# radiomodul.net
KiCad netlist of a schematic drawn in EAGLE
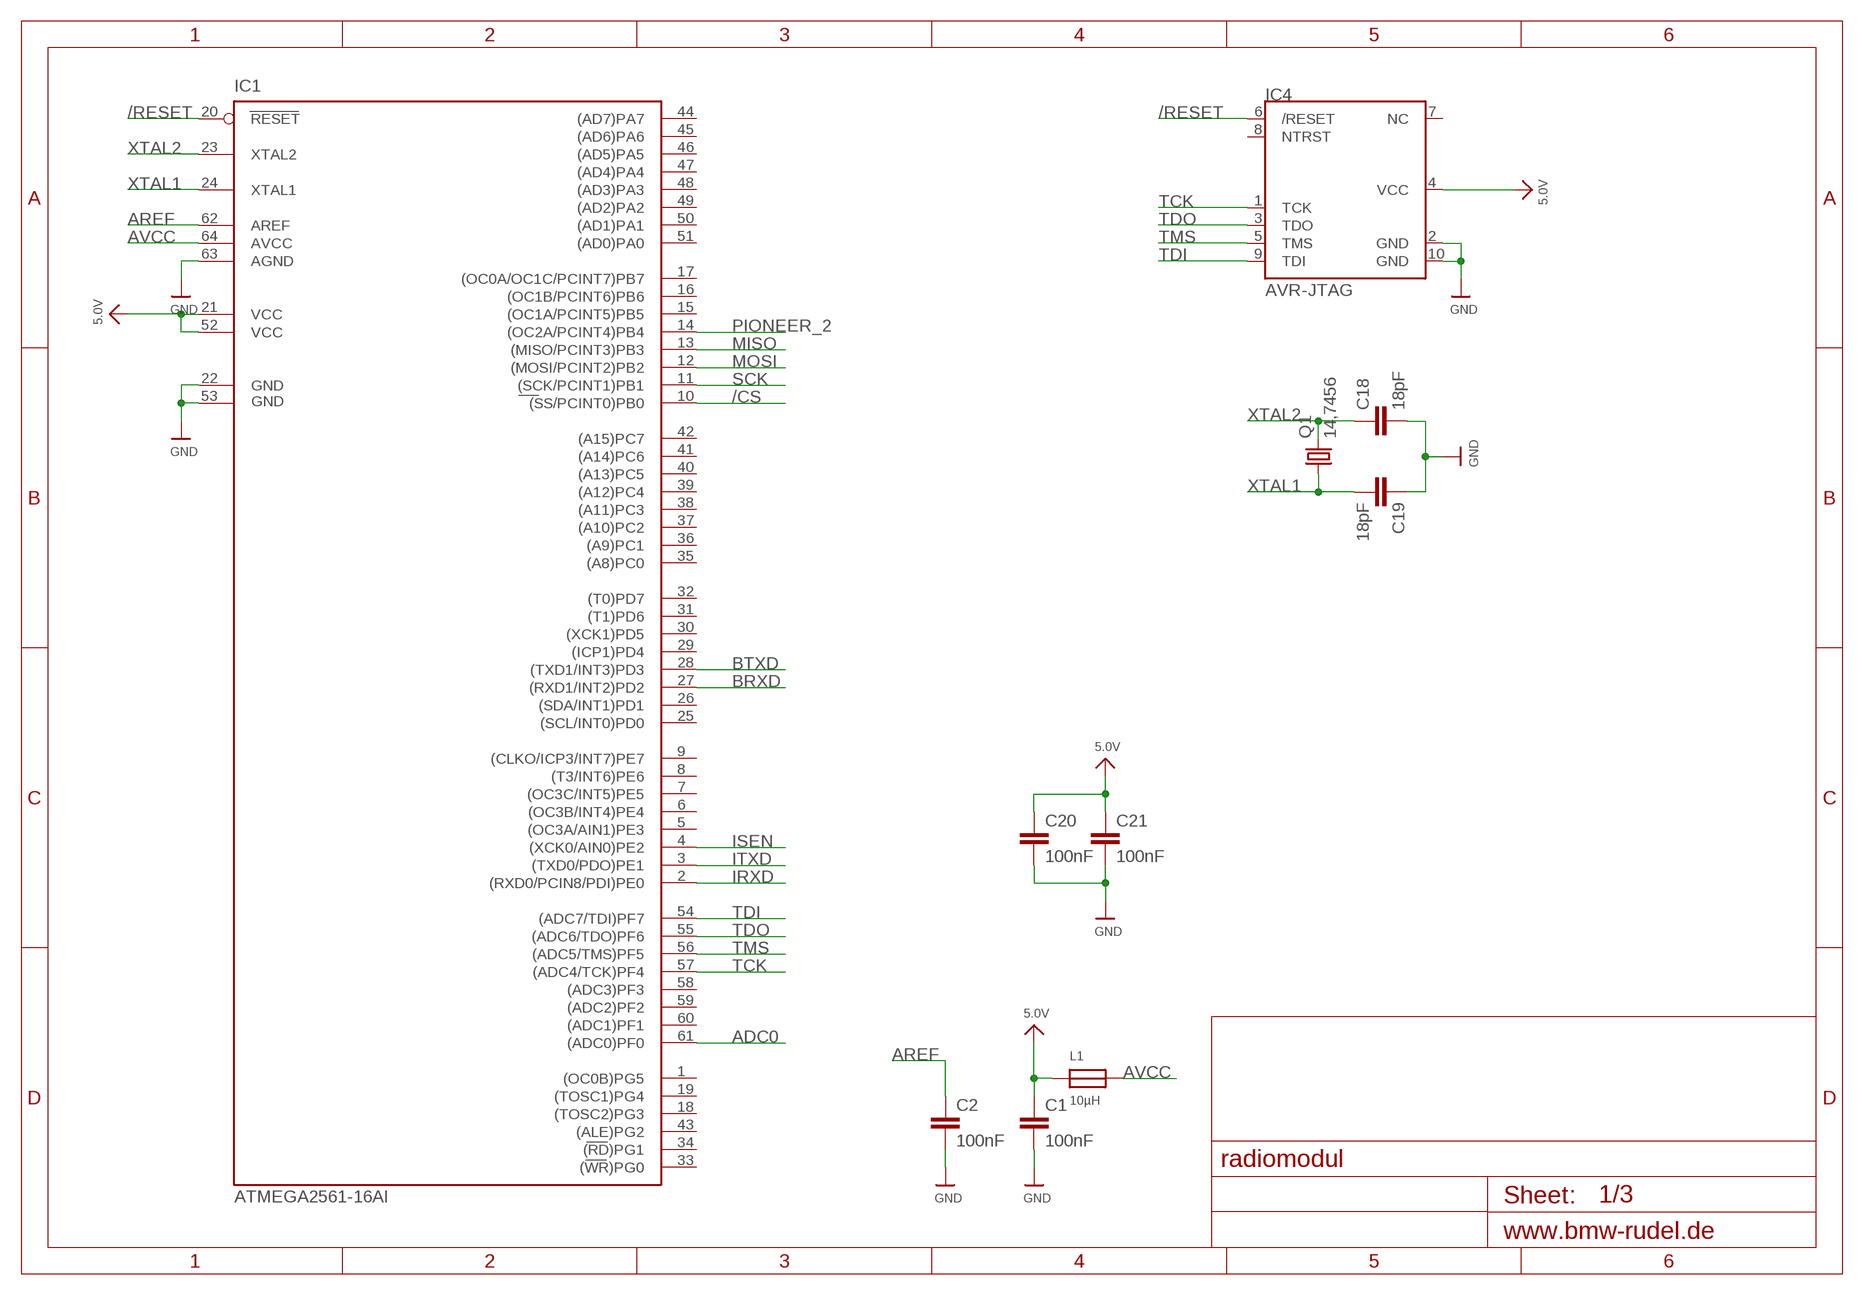
[diagram p0: schematic, sheet 1]
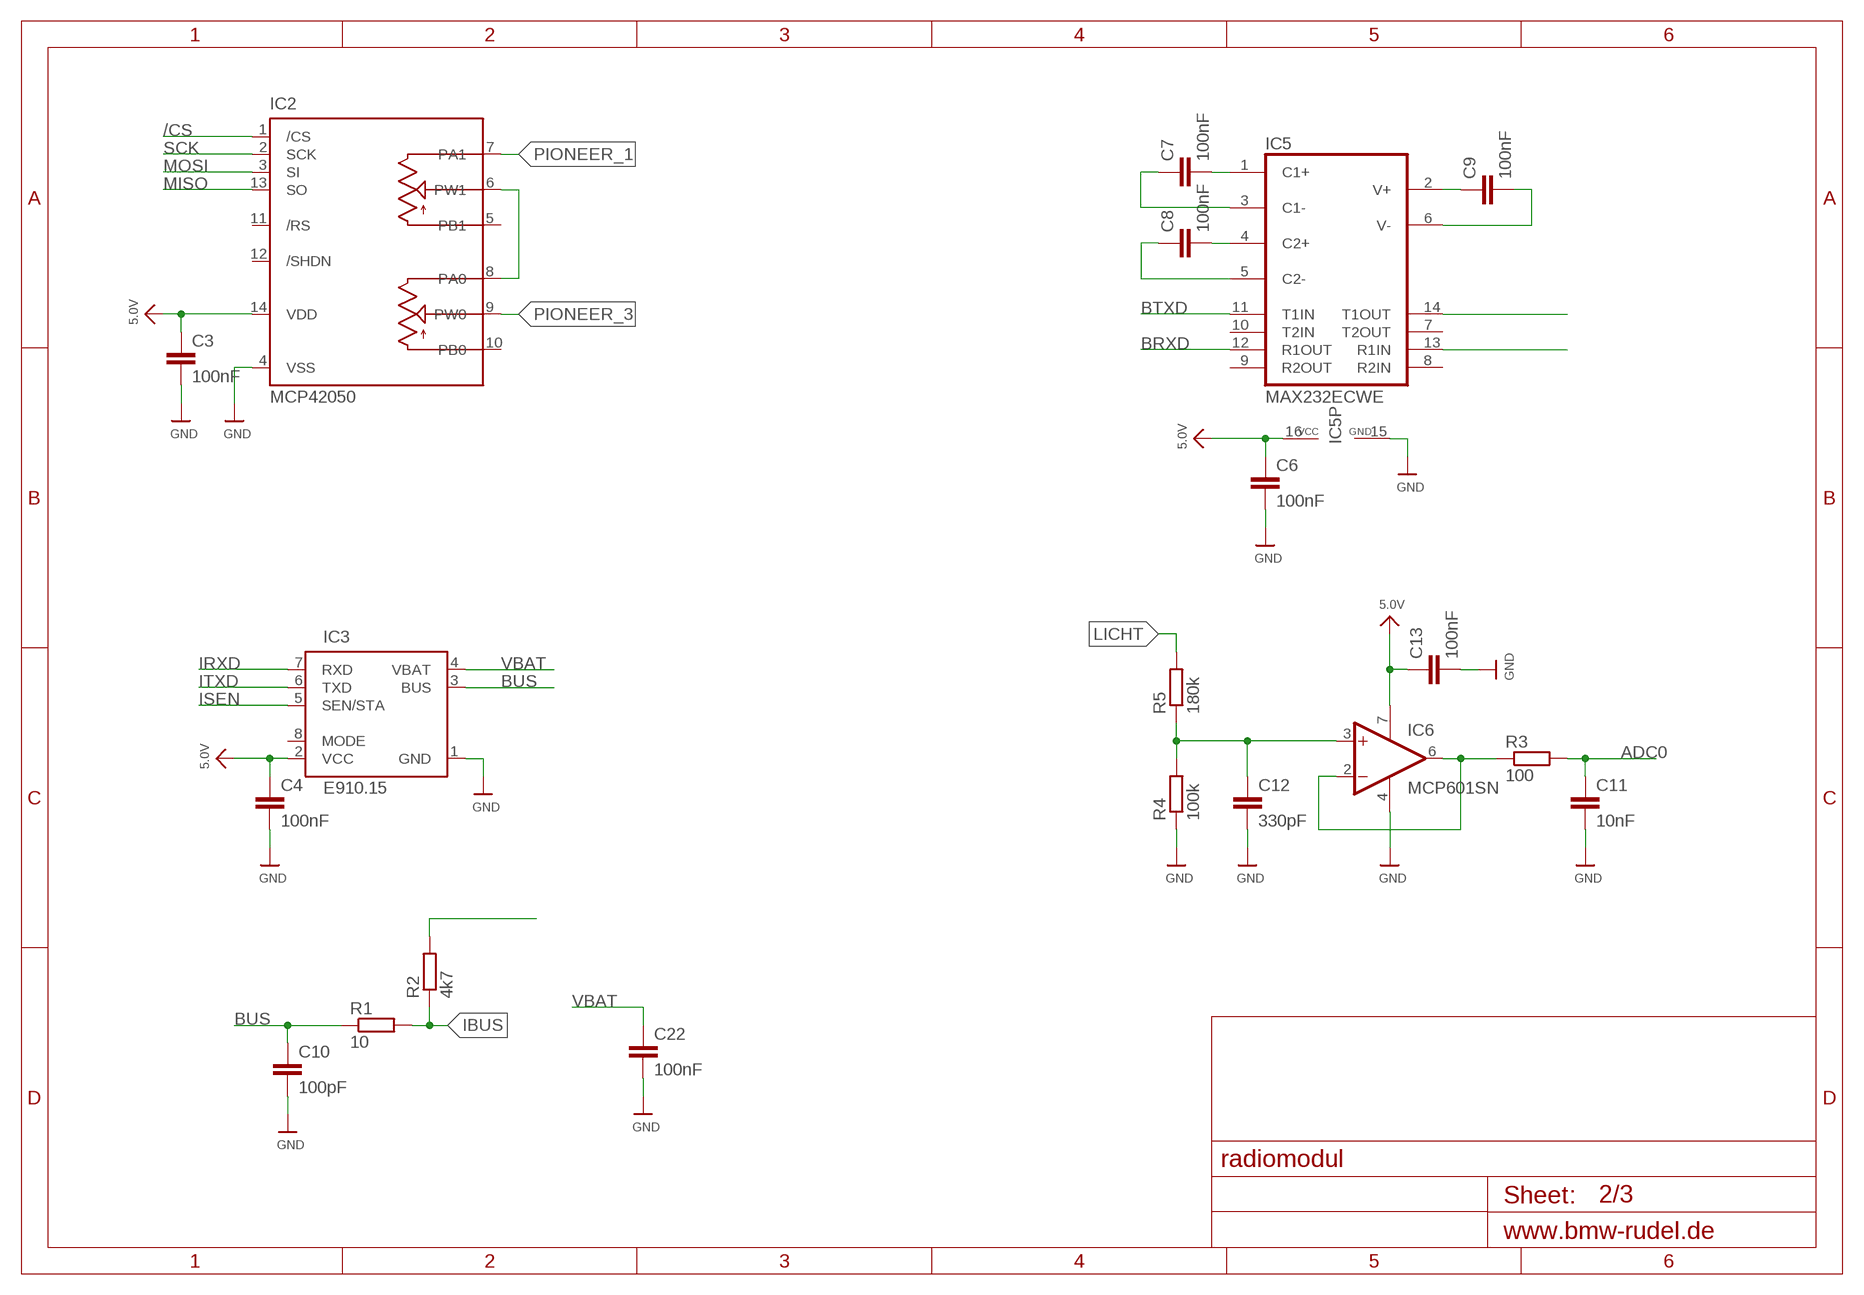
[diagram p1: schematic, sheet 2]
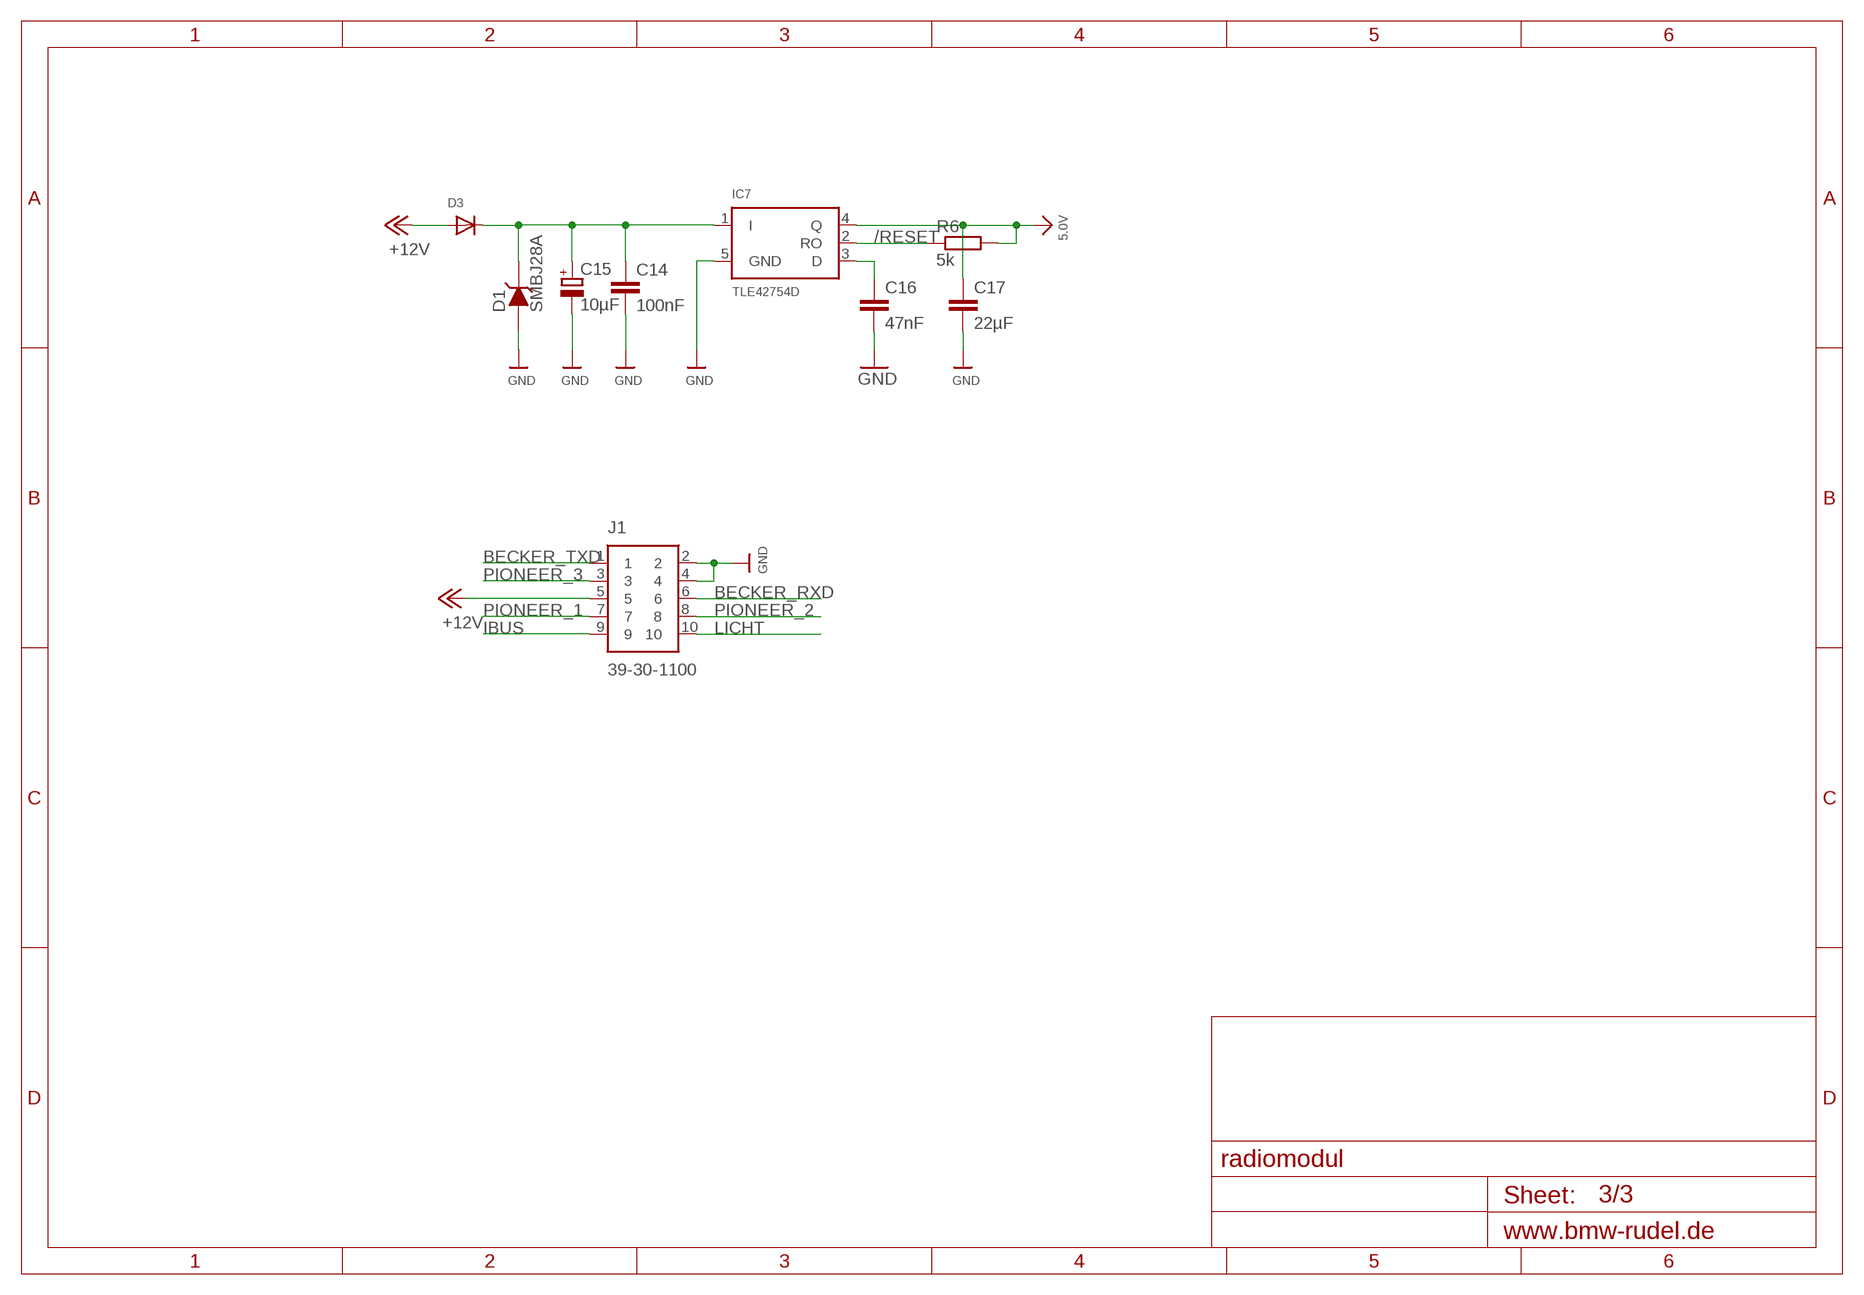
[diagram p2: schematic, sheet 3]

(export (version "E")
  (design (tool "Eeschema 10.0.6"))
  (components
    (comp (ref "C1")
      (value "100nF")
      (footprint "eagle-import:C0805")
      (libsource (lib "eagle-import") (part "C-EUC0805"))
    )
    (comp (ref "C2")
      (value "100nF")
      (footprint "eagle-import:C0805")
      (libsource (lib "eagle-import") (part "C-EUC0805"))
    )
    (comp (ref "C18")
      (value "18pF")
      (footprint "eagle-import:C0805")
      (libsource (lib "eagle-import") (part "C-EUC0805"))
    )
    (comp (ref "C19")
      (value "18pF")
      (footprint "eagle-import:C0805")
      (libsource (lib "eagle-import") (part "C-EUC0805"))
    )
    (comp (ref "C20")
      (value "100nF")
      (footprint "eagle-import:C0805")
      (libsource (lib "eagle-import") (part "C-EUC0805"))
    )
    (comp (ref "C21")
      (value "100nF")
      (footprint "eagle-import:C0805")
      (libsource (lib "eagle-import") (part "C-EUC0805"))
    )
    (comp (ref "IC1")
      (value "ATMEGA2561-16AI")
      (footprint "eagle-import:TQFP64")
      (libsource (lib "eagle-import") (part "ATMEGA2561AI-16"))
    )
    (comp (ref "IC4")
      (value "AVR-JTAG")
      (footprint "eagle-import:2X05_1.27MM_SMT")
      (libsource (lib "eagle-import") (part "AVR-JTAG"))
    )
    (comp (ref "L1")
      (value "10µH")
      (footprint "eagle-import:1206")
      (libsource (lib "eagle-import") (part "FERRITE1206"))
    )
    (comp (ref "Q1")
      (value "14,7456")
      (footprint "eagle-import:HC49UP")
      (libsource (lib "eagle-import") (part "CRYSTALHC49UP"))
    )
    (comp (ref "C3")
      (value "100nF")
      (footprint "eagle-import:C0805")
      (libsource (lib "eagle-import") (part "C-EUC0805"))
    )
    (comp (ref "C4")
      (value "100nF")
      (footprint "eagle-import:C0805")
      (libsource (lib "eagle-import") (part "C-EUC0805"))
    )
    (comp (ref "C6")
      (value "100nF")
      (footprint "eagle-import:C0805")
      (libsource (lib "eagle-import") (part "C-EUC0805"))
    )
    (comp (ref "C7")
      (value "100nF")
      (footprint "eagle-import:C0805")
      (libsource (lib "eagle-import") (part "C-EUC0805"))
    )
    (comp (ref "C8")
      (value "100nF")
      (footprint "eagle-import:C0805")
      (libsource (lib "eagle-import") (part "C-EUC0805"))
    )
    (comp (ref "C9")
      (value "100nF")
      (footprint "eagle-import:C0805")
      (libsource (lib "eagle-import") (part "C-EUC0805"))
    )
    (comp (ref "C10")
      (value "100pF")
      (footprint "eagle-import:C0805")
      (libsource (lib "eagle-import") (part "C-EUC0805"))
    )
    (comp (ref "C11")
      (value "10nF")
      (footprint "eagle-import:C0805")
      (libsource (lib "eagle-import") (part "C-EUC0805"))
    )
    (comp (ref "C12")
      (value "330pF")
      (footprint "eagle-import:C0805")
      (libsource (lib "eagle-import") (part "C-EUC0805"))
    )
    (comp (ref "C13")
      (value "100nF")
      (footprint "eagle-import:C0805")
      (libsource (lib "eagle-import") (part "C-EUC0805"))
    )
    (comp (ref "C22")
      (value "100nF")
      (footprint "eagle-import:C0805")
      (libsource (lib "eagle-import") (part "C-EUC0805"))
    )
    (comp (ref "IC2")
      (value "MCP42050")
      (footprint "eagle-import:SO-14")
      (libsource (lib "eagle-import") (part "MCP42050"))
    )
    (comp (ref "IC3")
      (value "E910.15")
      (footprint "eagle-import:SO8")
      (libsource (lib "eagle-import") (part "E910.15"))
    )
    (comp (ref "IC5")
      (value "MAX232ECWE")
      (footprint "eagle-import:SO16L")
      (fields (field (name "MF") "MAXIM") (field (name "MPN") "MAX232ECWE+"))
      (libsource (lib "eagle-import") (part "MAX232ECWE"))
    )
    (comp (ref "IC6")
      (value "MCP601SN")
      (footprint "eagle-import:SO08")
      (libsource (lib "eagle-import") (part "MCP601SN"))
    )
    (comp (ref "R1")
      (value "10")
      (footprint "eagle-import:R0805")
      (libsource (lib "eagle-import") (part "R-EU_R0805"))
    )
    (comp (ref "R2")
      (value "4k7")
      (footprint "eagle-import:R0805")
      (libsource (lib "eagle-import") (part "R-EU_R0805"))
    )
    (comp (ref "R3")
      (value "100")
      (footprint "eagle-import:R0805")
      (libsource (lib "eagle-import") (part "R-EU_R0805"))
    )
    (comp (ref "R4")
      (value "100k")
      (footprint "eagle-import:R0805")
      (libsource (lib "eagle-import") (part "R-EU_R0805"))
    )
    (comp (ref "R5")
      (value "180k")
      (footprint "eagle-import:R0805")
      (libsource (lib "eagle-import") (part "R-EU_R0805"))
    )
    (comp (ref "C14")
      (value "100nF")
      (footprint "eagle-import:C0805")
      (libsource (lib "eagle-import") (part "C-EUC0805"))
    )
    (comp (ref "C15")
      (value "10µF")
      (footprint "eagle-import:PANASONIC_D")
      (libsource (lib "eagle-import") (part "CPOL-EUD"))
    )
    (comp (ref "C16")
      (value "47nF")
      (footprint "eagle-import:C0805")
      (libsource (lib "eagle-import") (part "C-EUC0805"))
    )
    (comp (ref "C17")
      (value "22µF")
      (footprint "eagle-import:C1206")
      (libsource (lib "eagle-import") (part "C-EUC1206"))
    )
    (comp (ref "D1")
      (value "SMBJ28A")
      (footprint "eagle-import:DO-214AA")
      (libsource (lib "eagle-import") (part "P6SMBXXASMB"))
    )
    (comp (ref "D3")
      (value "DIODESMA")
      (footprint "eagle-import:SMADIODE")
      (libsource (lib "eagle-import") (part "DIODESMA"))
    )
    (comp (ref "IC7")
      (value "TLE42754D")
      (footprint "eagle-import:TO252-51")
      (libsource (lib "eagle-import") (part "TLE42754D"))
    )
    (comp (ref "J1")
      (value "39-30-1100")
      (footprint "eagle-import:39-30-1100")
      (fields (field (name "MOUSER_PART_NUMBER") "538-39-30-1100") (field (name "RS_PART_NUMBER") "5109871P"))
      (libsource (lib "eagle-import") (part "39-30-1100"))
    )
    (comp (ref "R6")
      (value "5k")
      (footprint "eagle-import:R0805")
      (libsource (lib "eagle-import") (part "R-EU_R0805"))
    )
  )
  (nets
    (net (code "1") (name "+12V") (class "Default")
      (node (ref "D3") (pin "A") (pinfunction "A_A") (pintype "passive"))
      (node (ref "J1") (pin "5") (pinfunction "5_5") (pintype "bidirectional"))
    )
    (net (code "2") (name "5.0V") (class "Default")
      (node (ref "C1") (pin "1") (pinfunction "1_1") (pintype "passive"))
      (node (ref "C13") (pin "1") (pinfunction "1_1") (pintype "passive"))
      (node (ref "C17") (pin "1") (pinfunction "1_1") (pintype "passive"))
      (node (ref "C20") (pin "1") (pinfunction "1_1") (pintype "passive"))
      (node (ref "C21") (pin "1") (pinfunction "1_1") (pintype "passive"))
      (node (ref "C3") (pin "1") (pinfunction "1_1") (pintype "passive"))
      (node (ref "C4") (pin "1") (pinfunction "1_1") (pintype "passive"))
      (node (ref "C6") (pin "1") (pinfunction "1_1") (pintype "passive"))
      (node (ref "IC1") (pin "21") (pinfunction "VCC_21") (pintype "power_in"))
      (node (ref "IC1") (pin "52") (pinfunction "VCC1_52") (pintype "power_in"))
      (node (ref "IC2") (pin "14") (pinfunction "VDD_14") (pintype "power_in"))
      (node (ref "IC3") (pin "2") (pinfunction "VCC_2") (pintype "power_in"))
      (node (ref "IC4") (pin "4") (pinfunction "VCC_4") (pintype "bidirectional"))
      (node (ref "IC5") (pin "16") (pinfunction "VCC_16") (pintype "power_in"))
      (node (ref "IC6") (pin "7") (pinfunction "V+_7") (pintype "power_in"))
      (node (ref "IC7") (pin "4") (pinfunction "Q_4") (pintype "bidirectional"))
      (node (ref "L1") (pin "1") (pinfunction "P$1_1") (pintype "bidirectional"))
      (node (ref "R6") (pin "2") (pinfunction "2_2") (pintype "passive"))
    )
    (net (code "3") (name "ADC0") (class "Default")
      (node (ref "C11") (pin "1") (pinfunction "1_1") (pintype "passive"))
      (node (ref "IC1") (pin "61") (pinfunction "(ADC0)PF0_61") (pintype "bidirectional"))
      (node (ref "R3") (pin "2") (pinfunction "2_2") (pintype "passive"))
    )
    (net (code "4") (name "AREF") (class "Default")
      (node (ref "C2") (pin "1") (pinfunction "1_1") (pintype "passive"))
      (node (ref "IC1") (pin "62") (pinfunction "AREF_62") (pintype "bidirectional"))
    )
    (net (code "5") (name "AVCC") (class "Default")
      (node (ref "IC1") (pin "64") (pinfunction "AVCC_64") (pintype "power_in"))
      (node (ref "L1") (pin "2") (pinfunction "P$2_2") (pintype "bidirectional"))
    )
    (net (code "6") (name "BECKER_RXD") (class "Default")
      (node (ref "IC5") (pin "13") (pinfunction "R1IN_13") (pintype "input"))
      (node (ref "J1") (pin "6") (pinfunction "6_6") (pintype "bidirectional"))
    )
    (net (code "7") (name "BECKER_TXD") (class "Default")
      (node (ref "IC5") (pin "14") (pinfunction "T1OUT_14") (pintype "output"))
      (node (ref "J1") (pin "1") (pinfunction "1_1") (pintype "bidirectional"))
    )
    (net (code "8") (name "BRXD") (class "Default")
      (node (ref "IC1") (pin "27") (pinfunction "(RXD1/INT2)PD2_27") (pintype "bidirectional"))
      (node (ref "IC5") (pin "12") (pinfunction "R1OUT_12") (pintype "output"))
    )
    (net (code "9") (name "BTXD") (class "Default")
      (node (ref "IC1") (pin "28") (pinfunction "(TXD1/INT3)PD3_28") (pintype "bidirectional"))
      (node (ref "IC5") (pin "11") (pinfunction "T1IN_11") (pintype "input"))
    )
    (net (code "10") (name "BUS") (class "Default")
      (node (ref "C10") (pin "1") (pinfunction "1_1") (pintype "passive"))
      (node (ref "IC3") (pin "3") (pinfunction "BUS_3") (pintype "bidirectional"))
      (node (ref "R1") (pin "1") (pinfunction "1_1") (pintype "passive"))
    )
    (net (code "11") (name "GND") (class "Default")
      (node (ref "C1") (pin "2") (pinfunction "2_2") (pintype "passive"))
      (node (ref "C10") (pin "2") (pinfunction "2_2") (pintype "passive"))
      (node (ref "C11") (pin "2") (pinfunction "2_2") (pintype "passive"))
      (node (ref "C12") (pin "2") (pinfunction "2_2") (pintype "passive"))
      (node (ref "C13") (pin "2") (pinfunction "2_2") (pintype "passive"))
      (node (ref "C14") (pin "2") (pinfunction "2_2") (pintype "passive"))
      (node (ref "C15") (pin "-") (pinfunction "-_-") (pintype "passive"))
      (node (ref "C16") (pin "2") (pinfunction "2_2") (pintype "passive"))
      (node (ref "C17") (pin "2") (pinfunction "2_2") (pintype "passive"))
      (node (ref "C18") (pin "2") (pinfunction "2_2") (pintype "passive"))
      (node (ref "C19") (pin "1") (pinfunction "1_1") (pintype "passive"))
      (node (ref "C2") (pin "2") (pinfunction "2_2") (pintype "passive"))
      (node (ref "C20") (pin "2") (pinfunction "2_2") (pintype "passive"))
      (node (ref "C21") (pin "2") (pinfunction "2_2") (pintype "passive"))
      (node (ref "C22") (pin "2") (pinfunction "2_2") (pintype "passive"))
      (node (ref "C3") (pin "2") (pinfunction "2_2") (pintype "passive"))
      (node (ref "C4") (pin "2") (pinfunction "2_2") (pintype "passive"))
      (node (ref "C6") (pin "2") (pinfunction "2_2") (pintype "passive"))
      (node (ref "D1") (pin "P$2") (pinfunction "A_P$2") (pintype "passive"))
      (node (ref "IC1") (pin "22") (pinfunction "GND_22") (pintype "power_in"))
      (node (ref "IC1") (pin "53") (pinfunction "GND1_53") (pintype "power_in"))
      (node (ref "IC1") (pin "63") (pinfunction "AGND_63") (pintype "power_in"))
      (node (ref "IC2") (pin "4") (pinfunction "VSS_4") (pintype "power_in"))
      (node (ref "IC3") (pin "1") (pinfunction "GND_1") (pintype "power_in"))
      (node (ref "IC4") (pin "10") (pinfunction "GND_10") (pintype "bidirectional"))
      (node (ref "IC4") (pin "2") (pinfunction "GND_2") (pintype "bidirectional"))
      (node (ref "IC5") (pin "15") (pinfunction "GND_15") (pintype "power_in"))
      (node (ref "IC6") (pin "4") (pinfunction "V-_4") (pintype "power_in"))
      (node (ref "IC7") (pin "5") (pinfunction "GND_5") (pintype "bidirectional"))
      (node (ref "J1") (pin "2") (pinfunction "2_2") (pintype "bidirectional"))
      (node (ref "J1") (pin "4") (pinfunction "4_4") (pintype "bidirectional"))
      (node (ref "R4") (pin "1") (pinfunction "1_1") (pintype "passive"))
    )
    (net (code "12") (name "IBUS") (class "Default")
      (node (ref "J1") (pin "9") (pinfunction "9_9") (pintype "bidirectional"))
      (node (ref "R1") (pin "2") (pinfunction "2_2") (pintype "passive"))
      (node (ref "R2") (pin "1") (pinfunction "1_1") (pintype "passive"))
    )
    (net (code "13") (name "IRXD") (class "Default")
      (node (ref "IC1") (pin "2") (pinfunction "(RXD0/PCIN8/PDI)PE0_2") (pintype "bidirectional"))
      (node (ref "IC3") (pin "7") (pinfunction "RXD_7") (pintype "output"))
    )
    (net (code "14") (name "ISEN") (class "Default")
      (node (ref "IC1") (pin "4") (pinfunction "(XCK0/AIN0)PE2_4") (pintype "bidirectional"))
      (node (ref "IC3") (pin "5") (pinfunction "SEN/STA_5") (pintype "bidirectional"))
    )
    (net (code "15") (name "ITXD") (class "Default")
      (node (ref "IC1") (pin "3") (pinfunction "(TXD0/PDO)PE1_3") (pintype "bidirectional"))
      (node (ref "IC3") (pin "6") (pinfunction "TXD_6") (pintype "input"))
    )
    (net (code "16") (name "LICHT") (class "Default")
      (node (ref "J1") (pin "10") (pinfunction "10_10") (pintype "bidirectional"))
      (node (ref "R5") (pin "2") (pinfunction "2_2") (pintype "passive"))
    )
    (net (code "17") (name "MISO") (class "Default")
      (node (ref "IC1") (pin "13") (pinfunction "(MISO/PCINT3)PB3_13") (pintype "bidirectional"))
      (node (ref "IC2") (pin "13") (pinfunction "SO_13") (pintype "output"))
    )
    (net (code "18") (name "MOSI") (class "Default")
      (node (ref "IC1") (pin "12") (pinfunction "(MOSI/PCINT2)PB2_12") (pintype "bidirectional"))
      (node (ref "IC2") (pin "3") (pinfunction "SI_3") (pintype "input"))
    )
    (net (code "19") (name "Net-(IC2-PA0)") (class "Default")
      (node (ref "IC2") (pin "6") (pinfunction "PW1_6") (pintype "bidirectional"))
      (node (ref "IC2") (pin "8") (pinfunction "PA0_8") (pintype "bidirectional"))
    )
    (net (code "20") (name "Net-(IC5A-C1+)") (class "Default")
      (node (ref "C7") (pin "2") (pinfunction "2_2") (pintype "passive"))
      (node (ref "IC5") (pin "1") (pinfunction "C1+_1") (pintype "bidirectional"))
    )
    (net (code "21") (name "Net-(IC5A-C1-)") (class "Default")
      (node (ref "C7") (pin "1") (pinfunction "1_1") (pintype "passive"))
      (node (ref "IC5") (pin "3") (pinfunction "C1-_3") (pintype "bidirectional"))
    )
    (net (code "22") (name "Net-(IC5A-C2+)") (class "Default")
      (node (ref "C8") (pin "2") (pinfunction "2_2") (pintype "passive"))
      (node (ref "IC5") (pin "4") (pinfunction "C2+_4") (pintype "bidirectional"))
    )
    (net (code "23") (name "Net-(IC5A-C2-)") (class "Default")
      (node (ref "C8") (pin "1") (pinfunction "1_1") (pintype "passive"))
      (node (ref "IC5") (pin "5") (pinfunction "C2-_5") (pintype "bidirectional"))
    )
    (net (code "24") (name "Net-(IC5A-V+)") (class "Default")
      (node (ref "C9") (pin "1") (pinfunction "1_1") (pintype "passive"))
      (node (ref "IC5") (pin "2") (pinfunction "V+_2") (pintype "bidirectional"))
    )
    (net (code "25") (name "Net-(IC5A-V-)") (class "Default")
      (node (ref "C9") (pin "2") (pinfunction "2_2") (pintype "passive"))
      (node (ref "IC5") (pin "6") (pinfunction "V-_6") (pintype "bidirectional"))
    )
    (net (code "26") (name "Net-(IC6-+IN)") (class "Default")
      (node (ref "C12") (pin "1") (pinfunction "1_1") (pintype "passive"))
      (node (ref "IC6") (pin "3") (pinfunction "+IN_3") (pintype "input"))
      (node (ref "R4") (pin "2") (pinfunction "2_2") (pintype "passive"))
      (node (ref "R5") (pin "1") (pinfunction "1_1") (pintype "passive"))
    )
    (net (code "27") (name "Net-(IC6--IN)") (class "Default")
      (node (ref "IC6") (pin "2") (pinfunction "-IN_2") (pintype "input"))
      (node (ref "IC6") (pin "6") (pinfunction "OUT_6") (pintype "output"))
      (node (ref "R3") (pin "1") (pinfunction "1_1") (pintype "passive"))
    )
    (net (code "28") (name "Net-(IC7-D)") (class "Default")
      (node (ref "C16") (pin "1") (pinfunction "1_1") (pintype "passive"))
      (node (ref "IC7") (pin "3") (pinfunction "D_3") (pintype "bidirectional"))
    )
    (net (code "29") (name "PIONEER_1") (class "Default")
      (node (ref "IC2") (pin "7") (pinfunction "PA1_7") (pintype "bidirectional"))
      (node (ref "J1") (pin "7") (pinfunction "7_7") (pintype "bidirectional"))
    )
    (net (code "30") (name "PIONEER_2") (class "Default")
      (node (ref "IC1") (pin "14") (pinfunction "(OC2A/PCINT4)PB4_14") (pintype "bidirectional"))
      (node (ref "J1") (pin "8") (pinfunction "8_8") (pintype "bidirectional"))
    )
    (net (code "31") (name "PIONEER_3") (class "Default")
      (node (ref "IC2") (pin "9") (pinfunction "PW0_9") (pintype "bidirectional"))
      (node (ref "J1") (pin "3") (pinfunction "3_3") (pintype "bidirectional"))
    )
    (net (code "32") (name "SAFT") (class "Default")
      (node (ref "C14") (pin "1") (pinfunction "1_1") (pintype "passive"))
      (node (ref "C15") (pin "+") (pinfunction "+_+") (pintype "passive"))
      (node (ref "D1") (pin "P$1") (pinfunction "C_P$1") (pintype "passive"))
      (node (ref "D3") (pin "C") (pinfunction "C_C") (pintype "passive"))
      (node (ref "IC7") (pin "1") (pinfunction "I_1") (pintype "bidirectional"))
      (node (ref "R2") (pin "2") (pinfunction "2_2") (pintype "passive"))
    )
    (net (code "33") (name "SCK") (class "Default")
      (node (ref "IC1") (pin "11") (pinfunction "(SCK/PCINT1)PB1_11") (pintype "bidirectional"))
      (node (ref "IC2") (pin "2") (pinfunction "SCK_2") (pintype "input"))
    )
    (net (code "34") (name "TCK") (class "Default")
      (node (ref "IC1") (pin "57") (pinfunction "(ADC4/TCK)PF4_57") (pintype "bidirectional"))
      (node (ref "IC4") (pin "1") (pinfunction "TCK_1") (pintype "bidirectional"))
    )
    (net (code "35") (name "TDI") (class "Default")
      (node (ref "IC1") (pin "54") (pinfunction "(ADC7/TDI)PF7_54") (pintype "bidirectional"))
      (node (ref "IC4") (pin "9") (pinfunction "TDI_9") (pintype "bidirectional"))
    )
    (net (code "36") (name "TDO") (class "Default")
      (node (ref "IC1") (pin "55") (pinfunction "(ADC6/TDO)PF6_55") (pintype "bidirectional"))
      (node (ref "IC4") (pin "3") (pinfunction "TDO_3") (pintype "bidirectional"))
    )
    (net (code "37") (name "TMS") (class "Default")
      (node (ref "IC1") (pin "56") (pinfunction "(ADC5/TMS)PF5_56") (pintype "bidirectional"))
      (node (ref "IC4") (pin "5") (pinfunction "TMS_5") (pintype "bidirectional"))
    )
    (net (code "38") (name "VBAT") (class "Default")
      (node (ref "C22") (pin "1") (pinfunction "1_1") (pintype "passive"))
      (node (ref "IC3") (pin "4") (pinfunction "VBAT_4") (pintype "power_in"))
    )
    (net (code "39") (name "XTAL1") (class "Default")
      (node (ref "C19") (pin "2") (pinfunction "2_2") (pintype "passive"))
      (node (ref "IC1") (pin "24") (pinfunction "XTAL1_24") (pintype "input"))
      (node (ref "Q1") (pin "1") (pinfunction "1_1") (pintype "passive"))
    )
    (net (code "40") (name "XTAL2") (class "Default")
      (node (ref "C18") (pin "1") (pinfunction "1_1") (pintype "passive"))
      (node (ref "IC1") (pin "23") (pinfunction "XTAL2_23") (pintype "output"))
      (node (ref "Q1") (pin "2") (pinfunction "2_2") (pintype "passive"))
    )
    (net (code "41") (name "unconnected-(IC1-(A8)PC0-Pad35)") (class "Default")
      (node (ref "IC1") (pin "35") (pinfunction "(A8)PC0_35") (pintype "bidirectional"))
    )
    (net (code "42") (name "unconnected-(IC1-(A9)PC1-Pad36)") (class "Default")
      (node (ref "IC1") (pin "36") (pinfunction "(A9)PC1_36") (pintype "bidirectional"))
    )
    (net (code "43") (name "unconnected-(IC1-(A10)PC2-Pad37)") (class "Default")
      (node (ref "IC1") (pin "37") (pinfunction "(A10)PC2_37") (pintype "bidirectional"))
    )
    (net (code "44") (name "unconnected-(IC1-(A11)PC3-Pad38)") (class "Default")
      (node (ref "IC1") (pin "38") (pinfunction "(A11)PC3_38") (pintype "bidirectional"))
    )
    (net (code "45") (name "unconnected-(IC1-(A12)PC4-Pad39)") (class "Default")
      (node (ref "IC1") (pin "39") (pinfunction "(A12)PC4_39") (pintype "bidirectional"))
    )
    (net (code "46") (name "unconnected-(IC1-(A13)PC5-Pad40)") (class "Default")
      (node (ref "IC1") (pin "40") (pinfunction "(A13)PC5_40") (pintype "bidirectional"))
    )
    (net (code "47") (name "unconnected-(IC1-(A14)PC6-Pad41)") (class "Default")
      (node (ref "IC1") (pin "41") (pinfunction "(A14)PC6_41") (pintype "bidirectional"))
    )
    (net (code "48") (name "unconnected-(IC1-(A15)PC7-Pad42)") (class "Default")
      (node (ref "IC1") (pin "42") (pinfunction "(A15)PC7_42") (pintype "bidirectional"))
    )
    (net (code "49") (name "unconnected-(IC1-(AD0)PA0-Pad51)") (class "Default")
      (node (ref "IC1") (pin "51") (pinfunction "(AD0)PA0_51") (pintype "bidirectional"))
    )
    (net (code "50") (name "unconnected-(IC1-(AD1)PA1-Pad50)") (class "Default")
      (node (ref "IC1") (pin "50") (pinfunction "(AD1)PA1_50") (pintype "bidirectional"))
    )
    (net (code "51") (name "unconnected-(IC1-(AD2)PA2-Pad49)") (class "Default")
      (node (ref "IC1") (pin "49") (pinfunction "(AD2)PA2_49") (pintype "bidirectional"))
    )
    (net (code "52") (name "unconnected-(IC1-(AD3)PA3-Pad48)") (class "Default")
      (node (ref "IC1") (pin "48") (pinfunction "(AD3)PA3_48") (pintype "bidirectional"))
    )
    (net (code "53") (name "unconnected-(IC1-(AD4)PA4-Pad47)") (class "Default")
      (node (ref "IC1") (pin "47") (pinfunction "(AD4)PA4_47") (pintype "bidirectional"))
    )
    (net (code "54") (name "unconnected-(IC1-(AD5)PA5-Pad46)") (class "Default")
      (node (ref "IC1") (pin "46") (pinfunction "(AD5)PA5_46") (pintype "bidirectional"))
    )
    (net (code "55") (name "unconnected-(IC1-(AD6)PA6-Pad45)") (class "Default")
      (node (ref "IC1") (pin "45") (pinfunction "(AD6)PA6_45") (pintype "bidirectional"))
    )
    (net (code "56") (name "unconnected-(IC1-(AD7)PA7-Pad44)") (class "Default")
      (node (ref "IC1") (pin "44") (pinfunction "(AD7)PA7_44") (pintype "bidirectional"))
    )
    (net (code "57") (name "unconnected-(IC1-(ADC1)PF1-Pad60)") (class "Default")
      (node (ref "IC1") (pin "60") (pinfunction "(ADC1)PF1_60") (pintype "bidirectional"))
    )
    (net (code "58") (name "unconnected-(IC1-(ADC2)PF2-Pad59)") (class "Default")
      (node (ref "IC1") (pin "59") (pinfunction "(ADC2)PF2_59") (pintype "bidirectional"))
    )
    (net (code "59") (name "unconnected-(IC1-(ADC3)PF3-Pad58)") (class "Default")
      (node (ref "IC1") (pin "58") (pinfunction "(ADC3)PF3_58") (pintype "bidirectional"))
    )
    (net (code "60") (name "unconnected-(IC1-(ALE)PG2-Pad43)") (class "Default")
      (node (ref "IC1") (pin "43") (pinfunction "(ALE)PG2_43") (pintype "bidirectional"))
    )
    (net (code "61") (name "unconnected-(IC1-(CLKO{slash}ICP3{slash}INT7)PE7-Pad9)") (class "Default")
      (node (ref "IC1") (pin "9") (pinfunction "(CLKO/ICP3/INT7)PE7_9") (pintype "bidirectional"))
    )
    (net (code "62") (name "unconnected-(IC1-(ICP1)PD4-Pad29)") (class "Default")
      (node (ref "IC1") (pin "29") (pinfunction "(ICP1)PD4_29") (pintype "bidirectional"))
    )
    (net (code "63") (name "unconnected-(IC1-(OC0A{slash}OC1C{slash}PCINT7)PB7-Pad17)") (class "Default")
      (node (ref "IC1") (pin "17") (pinfunction "(OC0A/OC1C/PCINT7)PB7_17") (pintype "bidirectional"))
    )
    (net (code "64") (name "unconnected-(IC1-(OC0B)PG5-Pad1)") (class "Default")
      (node (ref "IC1") (pin "1") (pinfunction "(OC0B)PG5_1") (pintype "bidirectional"))
    )
    (net (code "65") (name "unconnected-(IC1-(OC1A{slash}PCINT5)PB5-Pad15)") (class "Default")
      (node (ref "IC1") (pin "15") (pinfunction "(OC1A/PCINT5)PB5_15") (pintype "bidirectional"))
    )
    (net (code "66") (name "unconnected-(IC1-(OC1B{slash}PCINT6)PB6-Pad16)") (class "Default")
      (node (ref "IC1") (pin "16") (pinfunction "(OC1B/PCINT6)PB6_16") (pintype "bidirectional"))
    )
    (net (code "67") (name "unconnected-(IC1-(OC3A{slash}AIN1)PE3-Pad5)") (class "Default")
      (node (ref "IC1") (pin "5") (pinfunction "(OC3A/AIN1)PE3_5") (pintype "bidirectional"))
    )
    (net (code "68") (name "unconnected-(IC1-(OC3B{slash}INT4)PE4-Pad6)") (class "Default")
      (node (ref "IC1") (pin "6") (pinfunction "(OC3B/INT4)PE4_6") (pintype "bidirectional"))
    )
    (net (code "69") (name "unconnected-(IC1-(OC3C{slash}INT5)PE5-Pad7)") (class "Default")
      (node (ref "IC1") (pin "7") (pinfunction "(OC3C/INT5)PE5_7") (pintype "bidirectional"))
    )
    (net (code "70") (name "unconnected-(IC1-(RD)PG1-Pad34)") (class "Default")
      (node (ref "IC1") (pin "34") (pinfunction "(RD)PG1_34") (pintype "bidirectional"))
    )
    (net (code "71") (name "unconnected-(IC1-(SCL{slash}INT0)PD0-Pad25)") (class "Default")
      (node (ref "IC1") (pin "25") (pinfunction "(SCL/INT0)PD0_25") (pintype "bidirectional"))
    )
    (net (code "72") (name "unconnected-(IC1-(SDA{slash}INT1)PD1-Pad26)") (class "Default")
      (node (ref "IC1") (pin "26") (pinfunction "(SDA/INT1)PD1_26") (pintype "bidirectional"))
    )
    (net (code "73") (name "unconnected-(IC1-(T0)PD7-Pad32)") (class "Default")
      (node (ref "IC1") (pin "32") (pinfunction "(T0)PD7_32") (pintype "bidirectional"))
    )
    (net (code "74") (name "unconnected-(IC1-(T1)PD6-Pad31)") (class "Default")
      (node (ref "IC1") (pin "31") (pinfunction "(T1)PD6_31") (pintype "bidirectional"))
    )
    (net (code "75") (name "unconnected-(IC1-(T3{slash}INT6)PE6-Pad8)") (class "Default")
      (node (ref "IC1") (pin "8") (pinfunction "(T3/INT6)PE6_8") (pintype "bidirectional"))
    )
    (net (code "76") (name "unconnected-(IC1-(TOSC1)PG4-Pad19)") (class "Default")
      (node (ref "IC1") (pin "19") (pinfunction "(TOSC1)PG4_19") (pintype "bidirectional"))
    )
    (net (code "77") (name "unconnected-(IC1-(TOSC2)PG3-Pad18)") (class "Default")
      (node (ref "IC1") (pin "18") (pinfunction "(TOSC2)PG3_18") (pintype "bidirectional"))
    )
    (net (code "78") (name "unconnected-(IC1-(WR)PG0-Pad33)") (class "Default")
      (node (ref "IC1") (pin "33") (pinfunction "(WR)PG0_33") (pintype "bidirectional"))
    )
    (net (code "79") (name "unconnected-(IC1-(XCK1)PD5-Pad30)") (class "Default")
      (node (ref "IC1") (pin "30") (pinfunction "(XCK1)PD5_30") (pintype "bidirectional"))
    )
    (net (code "80") (name "unconnected-(IC2-PB0-Pad10)") (class "Default")
      (node (ref "IC2") (pin "10") (pinfunction "PB0_10") (pintype "bidirectional"))
    )
    (net (code "81") (name "unconnected-(IC2-PB1-Pad5)") (class "Default")
      (node (ref "IC2") (pin "5") (pinfunction "PB1_5") (pintype "bidirectional"))
    )
    (net (code "82") (name "unconnected-(IC2-{slash}RS-Pad11)") (class "Default")
      (node (ref "IC2") (pin "11") (pinfunction "/RS_11") (pintype "input"))
    )
    (net (code "83") (name "unconnected-(IC2-{slash}SHDN-Pad12)") (class "Default")
      (node (ref "IC2") (pin "12") (pinfunction "/SHDN_12") (pintype "input"))
    )
    (net (code "84") (name "unconnected-(IC3-MODE-Pad8)") (class "Default")
      (node (ref "IC3") (pin "8") (pinfunction "MODE_8") (pintype "input"))
    )
    (net (code "85") (name "unconnected-(IC4-NC-Pad7)") (class "Default")
      (node (ref "IC4") (pin "7") (pinfunction "NC_7") (pintype "no_connect"))
    )
    (net (code "86") (name "unconnected-(IC4-NTRST-Pad8)") (class "Default")
      (node (ref "IC4") (pin "8") (pinfunction "NTRST_8") (pintype "bidirectional"))
    )
    (net (code "87") (name "unconnected-(IC5A-R2IN-Pad8)") (class "Default")
      (node (ref "IC5") (pin "8") (pinfunction "R2IN_8") (pintype "input"))
    )
    (net (code "88") (name "unconnected-(IC5A-R2OUT-Pad9)") (class "Default")
      (node (ref "IC5") (pin "9") (pinfunction "R2OUT_9") (pintype "output"))
    )
    (net (code "89") (name "unconnected-(IC5A-T2IN-Pad10)") (class "Default")
      (node (ref "IC5") (pin "10") (pinfunction "T2IN_10") (pintype "input"))
    )
    (net (code "90") (name "unconnected-(IC5A-T2OUT-Pad7)") (class "Default")
      (node (ref "IC5") (pin "7") (pinfunction "T2OUT_7") (pintype "output"))
    )
    (net (code "91") (name "{slash}CS") (class "Default")
      (node (ref "IC1") (pin "10") (pinfunction "(SS/PCINT0)PB0_10") (pintype "bidirectional"))
      (node (ref "IC2") (pin "1") (pinfunction "/CS_1") (pintype "input"))
    )
    (net (code "92") (name "{slash}RESET") (class "Default")
      (node (ref "IC1") (pin "20") (pinfunction "RESET_20") (pintype "input"))
      (node (ref "IC4") (pin "6") (pinfunction "/RESET_6") (pintype "bidirectional"))
      (node (ref "IC7") (pin "2") (pinfunction "RO_2") (pintype "bidirectional"))
      (node (ref "R6") (pin "1") (pinfunction "1_1") (pintype "passive"))
    )
  )
)
